# I2C_GPIOEXPANDER_PCF8574.net
KiCad netlist of a schematic drawn in Altium Designer
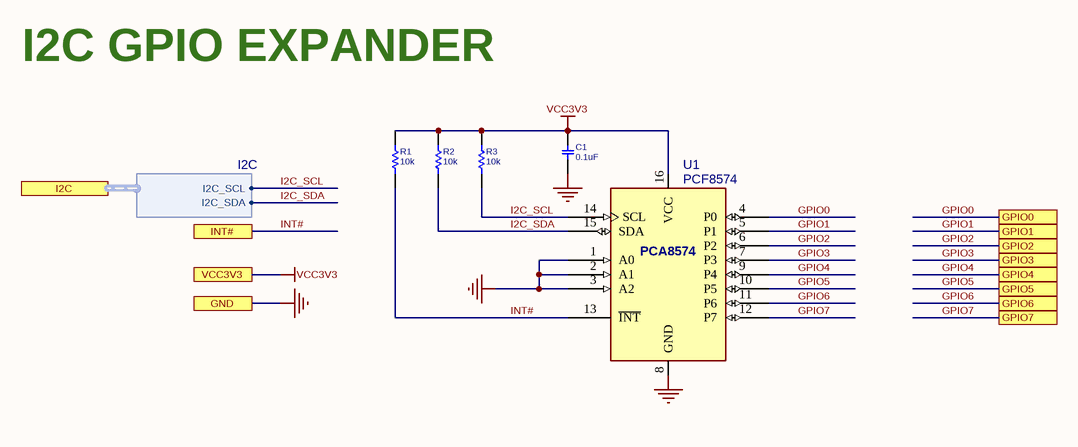
[diagram p0: I2C_GPIOEXPANDER_PCF8574.SchDoc]

(export (version "E")
  (design (tool "Eeschema 10.0.6"))
  (components
    (comp (ref "C1")
      (value "0.1uF")
      (footprint "C0603")
      (description "CAP, MLCC, -F, -V, MATERIAL, -%, 0201")
      (fields (field (name "MANF_P#") "MANF_PART#"))
      (libsource (lib "passive_smd") (part "CAP_SMD_MLCC_0805"))
    )
    (comp (ref "R1")
      (value "10k")
      (footprint "R0603")
      (description "RESISTOR, SMD")
      (libsource (lib "passive_smd") (part "RES_SMD_0603"))
    )
    (comp (ref "R2")
      (value "10k")
      (footprint "R0603")
      (description "RESISTOR, SMD")
      (libsource (lib "passive_smd") (part "RES_SMD_0603"))
    )
    (comp (ref "R3")
      (value "10k")
      (footprint "R0603")
      (description "RESISTOR, SMD")
      (libsource (lib "passive_smd") (part "RES_SMD_0603"))
    )
    (comp (ref "U1")
      (value "PCF8574")
      (footprint "SO_16_W")
      (description "IC, I2C IO Expander, 8CH, 100KHz")
      (fields (field (name "MANF") "Texas Instruments") (field (name "MANF_P#") "PCF8574DW"))
      (libsource (lib "i2c_io_expander") (part "PCF8574_SOP16W"))
    )
  )
  (nets
    (net (code "2") (name "/GPIO0") (class "Default")
      (node (ref "U1") (pin "4") (pinfunction "P0_4") (pintype "bidirectional"))
    )
    (net (code "3") (name "/GPIO1") (class "Default")
      (node (ref "U1") (pin "5") (pinfunction "P1_5") (pintype "bidirectional"))
    )
    (net (code "4") (name "/GPIO2") (class "Default")
      (node (ref "U1") (pin "6") (pinfunction "P2_6") (pintype "bidirectional"))
    )
    (net (code "5") (name "/GPIO3") (class "Default")
      (node (ref "U1") (pin "7") (pinfunction "P3_7") (pintype "bidirectional"))
    )
    (net (code "6") (name "/GPIO4") (class "Default")
      (node (ref "U1") (pin "9") (pinfunction "P4_9") (pintype "bidirectional"))
    )
    (net (code "7") (name "/GPIO5") (class "Default")
      (node (ref "U1") (pin "10") (pinfunction "P5_10") (pintype "bidirectional"))
    )
    (net (code "8") (name "/GPIO6") (class "Default")
      (node (ref "U1") (pin "11") (pinfunction "P6_11") (pintype "bidirectional"))
    )
    (net (code "9") (name "/GPIO7") (class "Default")
      (node (ref "U1") (pin "12") (pinfunction "P7_12") (pintype "bidirectional"))
    )
    (net (code "10") (name "/I2C_SCL") (class "Default")
      (node (ref "R3") (pin "1") (pinfunction "1_1") (pintype "passive"))
      (node (ref "U1") (pin "14") (pinfunction "SCL_14") (pintype "input"))
    )
    (net (code "11") (name "/I2C_SDA") (class "Default")
      (node (ref "R2") (pin "1") (pinfunction "1_1") (pintype "passive"))
      (node (ref "U1") (pin "15") (pinfunction "SDA_15") (pintype "bidirectional"))
    )
    (net (code "12") (name "/INT#") (class "Default")
      (node (ref "R1") (pin "1") (pinfunction "1_1") (pintype "passive"))
      (node (ref "U1") (pin "13") (pinfunction "~{INT}_13") (pintype "open_collector"))
    )
    (net (code "14") (name "GND") (class "Default")
      (node (ref "C1") (pin "1") (pinfunction "1_1") (pintype "passive"))
      (node (ref "U1") (pin "1") (pinfunction "A0_1") (pintype "input"))
      (node (ref "U1") (pin "2") (pinfunction "A1_2") (pintype "input"))
      (node (ref "U1") (pin "3") (pinfunction "A2_3") (pintype "input"))
      (node (ref "U1") (pin "8") (pinfunction "GND_8") (pintype "power_in"))
    )
    (net (code "15") (name "VCC3V3") (class "Default")
      (node (ref "C1") (pin "2") (pinfunction "2_2") (pintype "passive"))
      (node (ref "R1") (pin "2") (pinfunction "2_2") (pintype "passive"))
      (node (ref "R2") (pin "2") (pinfunction "2_2") (pintype "passive"))
      (node (ref "R3") (pin "2") (pinfunction "2_2") (pintype "passive"))
      (node (ref "U1") (pin "16") (pinfunction "VCC_16") (pintype "power_in"))
    )
  )
)
